# PINO.net
KiCad netlist of a schematic drawn in EAGLE
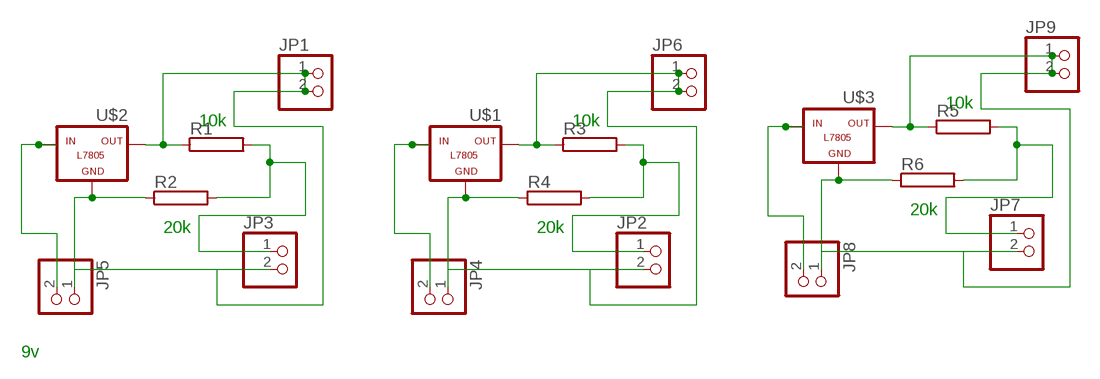
[diagram p0: schematic, sheet 1]

(export (version "E")
  (design (tool "Eeschema 10.0.6"))
  (components
    (comp (ref "JP1")
      (value "PINHD-1X2M")
      (footprint "eagle-import:1X02M")
      (libsource (lib "eagle-import") (part "PINHD-1X2M"))
    )
    (comp (ref "JP2")
      (value "PINHD-1X2M")
      (footprint "eagle-import:1X02M")
      (libsource (lib "eagle-import") (part "PINHD-1X2M"))
    )
    (comp (ref "JP3")
      (value "PINHD-1X2M")
      (footprint "eagle-import:1X02M")
      (libsource (lib "eagle-import") (part "PINHD-1X2M"))
    )
    (comp (ref "JP4")
      (value "PINHD-1X2M")
      (footprint "eagle-import:1X02M")
      (libsource (lib "eagle-import") (part "PINHD-1X2M"))
    )
    (comp (ref "JP5")
      (value "PINHD-1X2M")
      (footprint "eagle-import:1X02M")
      (libsource (lib "eagle-import") (part "PINHD-1X2M"))
    )
    (comp (ref "JP6")
      (value "PINHD-1X2M")
      (footprint "eagle-import:1X02M")
      (libsource (lib "eagle-import") (part "PINHD-1X2M"))
    )
    (comp (ref "JP7")
      (value "PINHD-1X2M")
      (footprint "eagle-import:1X02M")
      (libsource (lib "eagle-import") (part "PINHD-1X2M"))
    )
    (comp (ref "JP8")
      (value "PINHD-1X2M")
      (footprint "eagle-import:1X02M")
      (libsource (lib "eagle-import") (part "PINHD-1X2M"))
    )
    (comp (ref "JP9")
      (value "PINHD-1X2M")
      (footprint "eagle-import:1X02M")
      (libsource (lib "eagle-import") (part "PINHD-1X2M"))
    )
    (comp (ref "R1")
      (value "RCA4050")
      (footprint "eagle-import:CA4050")
      (libsource (lib "eagle-import") (part "RCA4050"))
    )
    (comp (ref "R2")
      (value "RCA4050")
      (footprint "eagle-import:CA4050")
      (libsource (lib "eagle-import") (part "RCA4050"))
    )
    (comp (ref "R3")
      (value "RCA4050")
      (footprint "eagle-import:CA4050")
      (libsource (lib "eagle-import") (part "RCA4050"))
    )
    (comp (ref "R4")
      (value "RCA4050")
      (footprint "eagle-import:CA4050")
      (libsource (lib "eagle-import") (part "RCA4050"))
    )
    (comp (ref "R5")
      (value "RCA4050")
      (footprint "eagle-import:CA4050")
      (libsource (lib "eagle-import") (part "RCA4050"))
    )
    (comp (ref "R6")
      (value "RCA4050")
      (footprint "eagle-import:CA4050")
      (libsource (lib "eagle-import") (part "RCA4050"))
    )
    (comp (ref "U$1")
      (value "-L7805")
      (footprint "eagle-import:L7805")
      (libsource (lib "eagle-import") (part "-L7805"))
    )
    (comp (ref "U$2")
      (value "-L7805")
      (footprint "eagle-import:L7805")
      (libsource (lib "eagle-import") (part "-L7805"))
    )
    (comp (ref "U$3")
      (value "-L7805")
      (footprint "eagle-import:L7805")
      (libsource (lib "eagle-import") (part "-L7805"))
    )
  )
  (nets
    (net (code "1") (name "Net-(JP1-Pad1)") (class "Default")
      (node (ref "JP1") (pin "1") (pinfunction "1_1") (pintype "passive"))
      (node (ref "JP1") (pin "2") (pinfunction "2_2") (pintype "passive"))
      (node (ref "JP3") (pin "2") (pinfunction "2_2") (pintype "passive"))
      (node (ref "JP5") (pin "1") (pinfunction "1_1") (pintype "passive"))
      (node (ref "R1") (pin "1") (pinfunction "1_1") (pintype "passive"))
      (node (ref "R2") (pin "1") (pinfunction "1_1") (pintype "passive"))
      (node (ref "U$2") (pin "GND") (pinfunction "GND_GND") (pintype "input"))
      (node (ref "U$2") (pin "OUT") (pinfunction "OUT_OUT") (pintype "passive"))
    )
    (net (code "2") (name "Net-(JP2-Pad1)") (class "Default")
      (node (ref "JP2") (pin "1") (pinfunction "1_1") (pintype "passive"))
      (node (ref "R3") (pin "2") (pinfunction "2_2") (pintype "passive"))
      (node (ref "R4") (pin "2") (pinfunction "2_2") (pintype "passive"))
    )
    (net (code "3") (name "Net-(JP2-Pad2)") (class "Default")
      (node (ref "JP2") (pin "2") (pinfunction "2_2") (pintype "passive"))
      (node (ref "JP4") (pin "1") (pinfunction "1_1") (pintype "passive"))
      (node (ref "JP6") (pin "1") (pinfunction "1_1") (pintype "passive"))
      (node (ref "JP6") (pin "2") (pinfunction "2_2") (pintype "passive"))
      (node (ref "R3") (pin "1") (pinfunction "1_1") (pintype "passive"))
      (node (ref "R4") (pin "1") (pinfunction "1_1") (pintype "passive"))
      (node (ref "U$1") (pin "GND") (pinfunction "GND_GND") (pintype "input"))
      (node (ref "U$1") (pin "OUT") (pinfunction "OUT_OUT") (pintype "passive"))
    )
    (net (code "4") (name "Net-(JP3-Pad1)") (class "Default")
      (node (ref "JP3") (pin "1") (pinfunction "1_1") (pintype "passive"))
      (node (ref "R1") (pin "2") (pinfunction "2_2") (pintype "passive"))
      (node (ref "R2") (pin "2") (pinfunction "2_2") (pintype "passive"))
    )
    (net (code "5") (name "Net-(JP4-Pad2)") (class "Default")
      (node (ref "JP4") (pin "2") (pinfunction "2_2") (pintype "passive"))
      (node (ref "U$1") (pin "IN") (pinfunction "IN_IN") (pintype "input"))
    )
    (net (code "6") (name "Net-(JP5-Pad2)") (class "Default")
      (node (ref "JP5") (pin "2") (pinfunction "2_2") (pintype "passive"))
      (node (ref "U$2") (pin "IN") (pinfunction "IN_IN") (pintype "input"))
    )
    (net (code "7") (name "Net-(JP7-Pad1)") (class "Default")
      (node (ref "JP7") (pin "1") (pinfunction "1_1") (pintype "passive"))
      (node (ref "R5") (pin "2") (pinfunction "2_2") (pintype "passive"))
      (node (ref "R6") (pin "2") (pinfunction "2_2") (pintype "passive"))
    )
    (net (code "8") (name "Net-(JP7-Pad2)") (class "Default")
      (node (ref "JP7") (pin "2") (pinfunction "2_2") (pintype "passive"))
      (node (ref "JP8") (pin "1") (pinfunction "1_1") (pintype "passive"))
      (node (ref "JP9") (pin "1") (pinfunction "1_1") (pintype "passive"))
      (node (ref "JP9") (pin "2") (pinfunction "2_2") (pintype "passive"))
      (node (ref "R5") (pin "1") (pinfunction "1_1") (pintype "passive"))
      (node (ref "R6") (pin "1") (pinfunction "1_1") (pintype "passive"))
      (node (ref "U$3") (pin "GND") (pinfunction "GND_GND") (pintype "input"))
      (node (ref "U$3") (pin "OUT") (pinfunction "OUT_OUT") (pintype "passive"))
    )
    (net (code "9") (name "Net-(JP8-Pad2)") (class "Default")
      (node (ref "JP8") (pin "2") (pinfunction "2_2") (pintype "passive"))
      (node (ref "U$3") (pin "IN") (pinfunction "IN_IN") (pintype "input"))
    )
  )
)
